# FrontPannel.net
KiCad netlist of a schematic drawn in Altium Designer
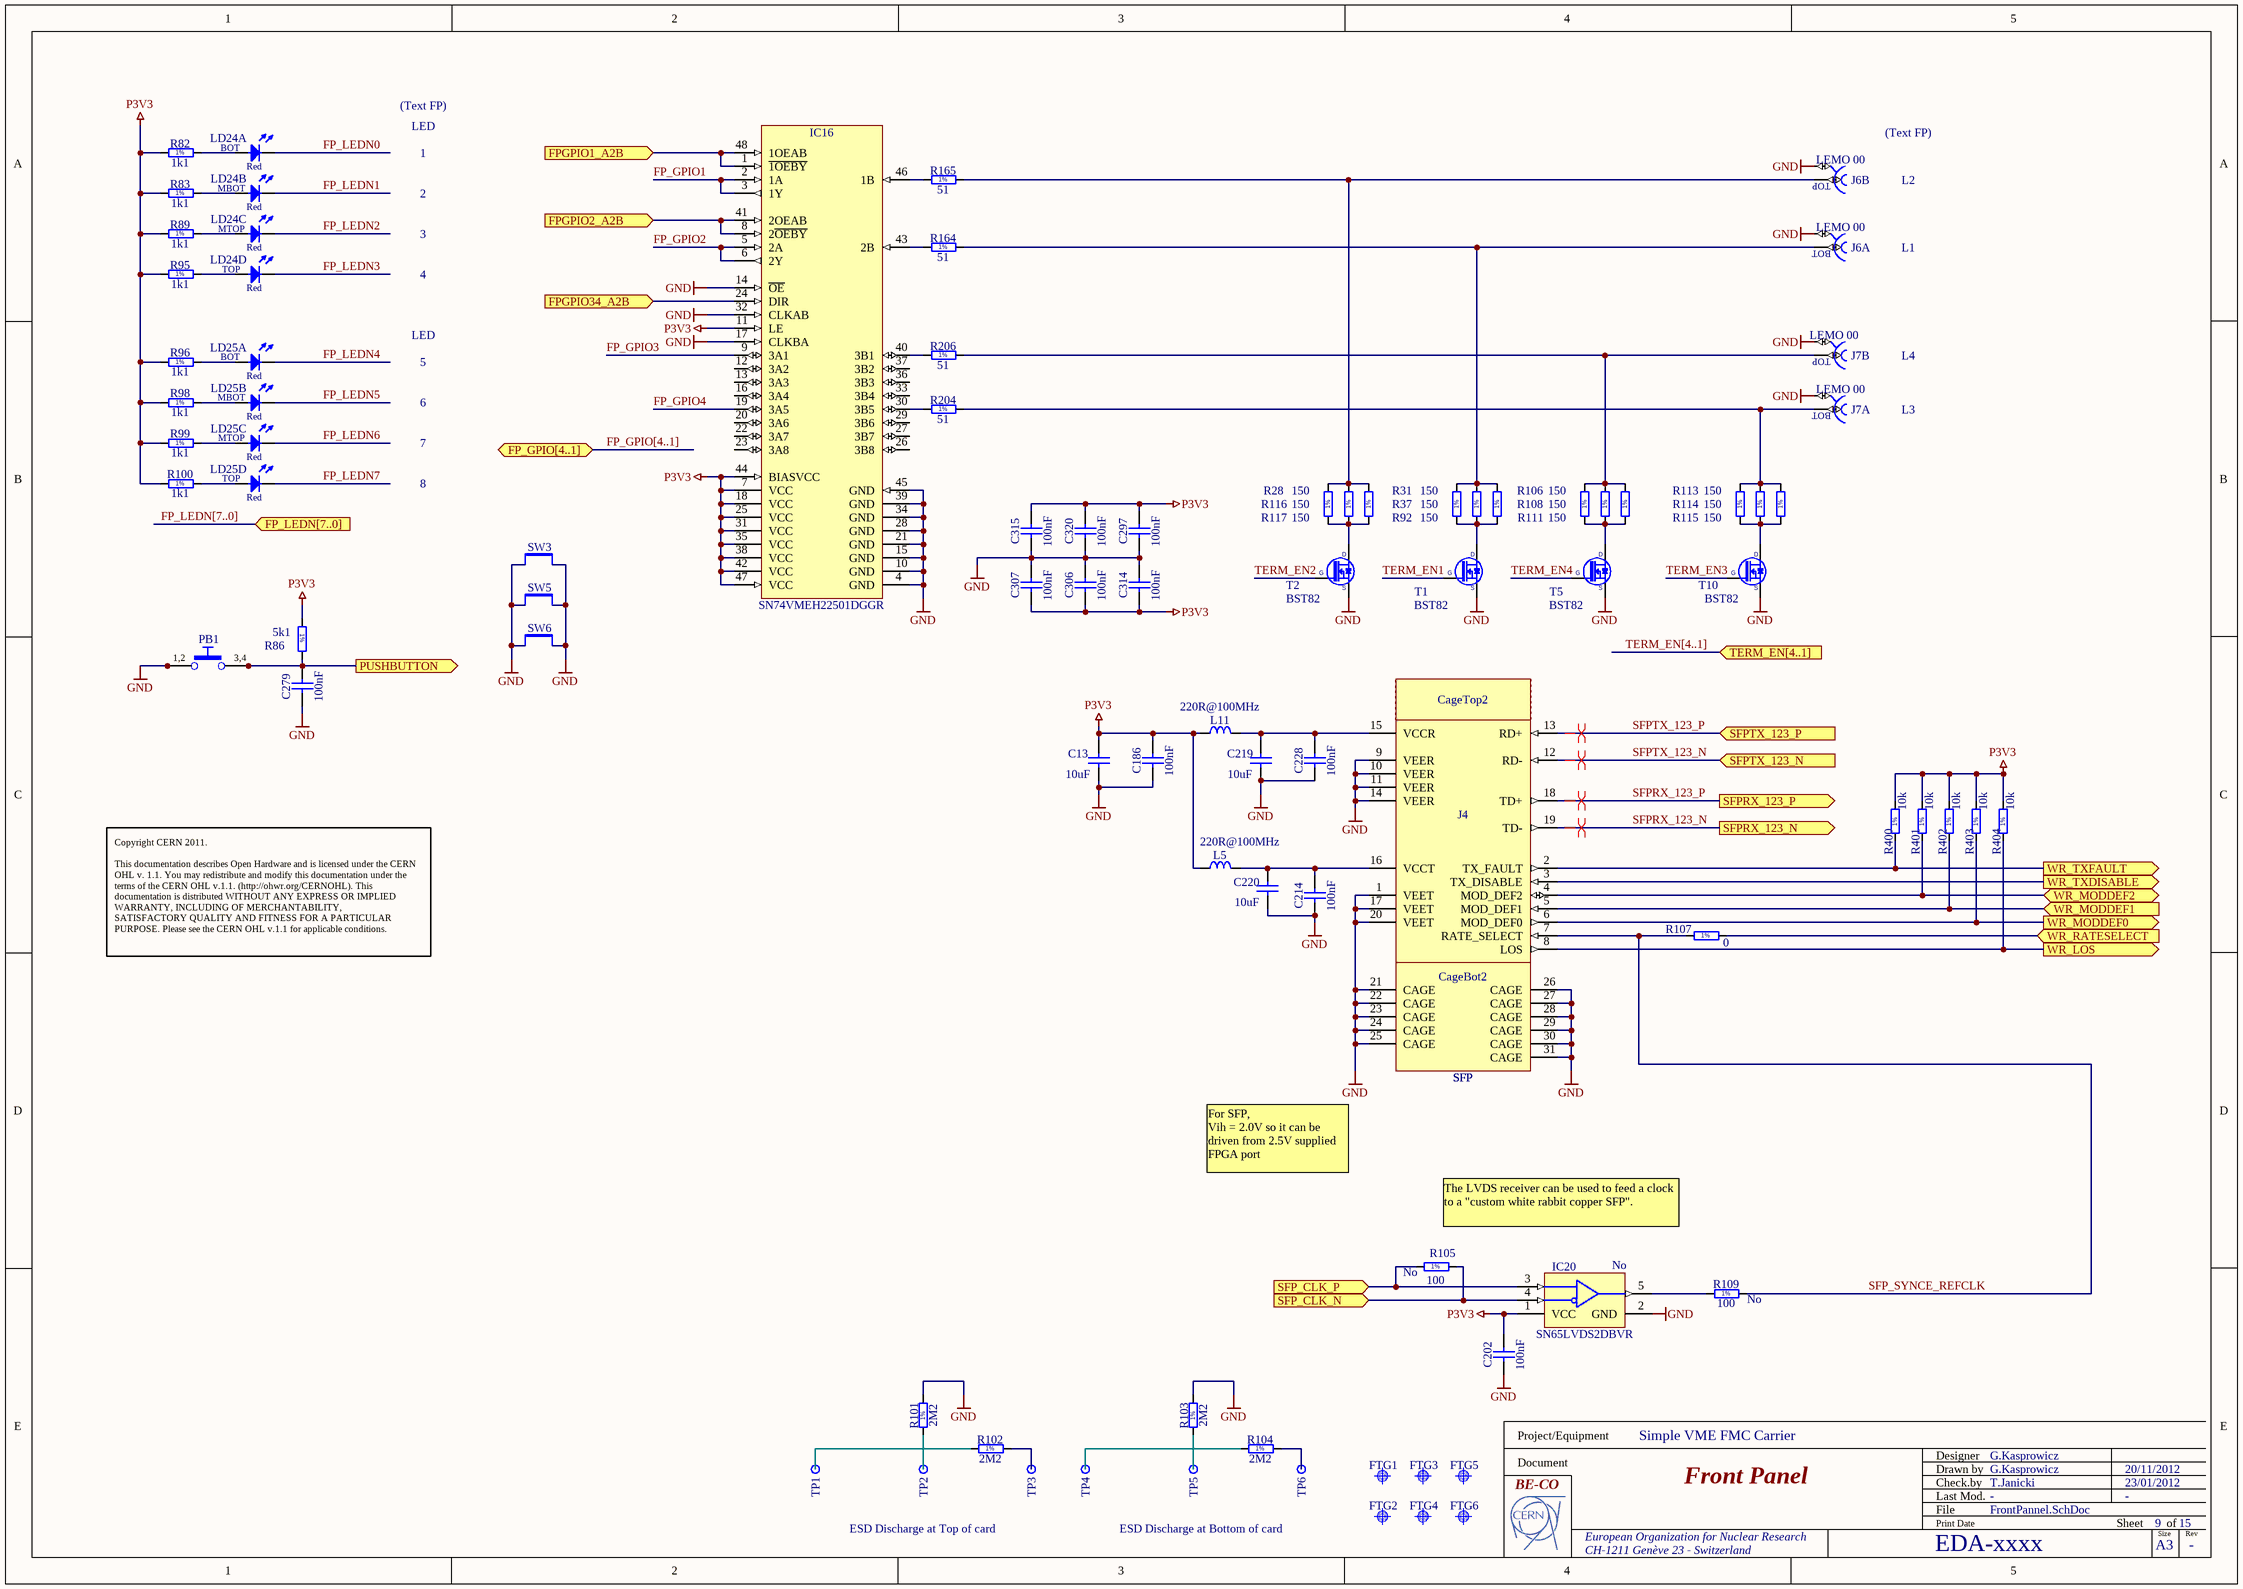
[diagram p0: FrontPannel.SchDoc]

(export (version "E")
  (design (tool "Eeschema 10.0.6"))
  (components
    (comp (ref "C13")
      (value "10uF")
      (footprint "CAPC3225X270N")
      (description "Non-polarised capacitor")
      (fields
        (field (name "PART NUMBER") "CC1210_10UF_25V_10%_X7R")
        (field (name "VOLTAGE") "25V")
        (field (name "AUTHOR") "CERN DEM JLC")
      )
      (libsource (lib "Capacitors") (part "Capacitor - non polarized"))
    )
    (comp (ref "C186")
      (value "100nF")
      (footprint "CAPC1005X55N")
      (description "Non-polarised capacitor")
      (fields
        (field (name "PART NUMBER") "CC0402_100NF_16V_10%_X7R")
        (field (name "VOLTAGE") "16V")
        (field (name "AUTHOR") "CERN DEM JLC")
      )
      (libsource (lib "Capacitors") (part "Capacitor - non polarized"))
    )
    (comp (ref "C202")
      (value "100nF")
      (footprint "CAPC1005X55N")
      (description "Non-polarised capacitor")
      (fields
        (field (name "PART NUMBER") "CC0402_100NF_16V_10%_X7R")
        (field (name "VOLTAGE") "16V")
        (field (name "AUTHOR") "CERN DEM JLC")
      )
      (libsource (lib "Capacitors") (part "Capacitor - non polarized"))
    )
    (comp (ref "C214")
      (value "100nF")
      (footprint "CAPC1005X55N")
      (description "Non-polarised capacitor")
      (fields
        (field (name "PART NUMBER") "CC0402_100NF_16V_10%_X7R")
        (field (name "VOLTAGE") "16V")
        (field (name "AUTHOR") "CERN DEM JLC")
      )
      (libsource (lib "Capacitors") (part "Capacitor - non polarized"))
    )
    (comp (ref "C219")
      (value "10uF")
      (footprint "CAPC3225X270N")
      (description "Non-polarised capacitor")
      (fields
        (field (name "PART NUMBER") "CC1210_10UF_25V_10%_X7R")
        (field (name "VOLTAGE") "25V")
        (field (name "AUTHOR") "CERN DEM JLC")
      )
      (libsource (lib "Capacitors") (part "Capacitor - non polarized"))
    )
    (comp (ref "C220")
      (value "10uF")
      (footprint "CAPC3225X270N")
      (description "Non-polarised capacitor")
      (fields
        (field (name "PART NUMBER") "CC1210_10UF_25V_10%_X7R")
        (field (name "VOLTAGE") "25V")
        (field (name "AUTHOR") "CERN DEM JLC")
      )
      (libsource (lib "Capacitors") (part "Capacitor - non polarized"))
    )
    (comp (ref "C228")
      (value "100nF")
      (footprint "CAPC1005X55N")
      (description "Non-polarised capacitor")
      (fields
        (field (name "PART NUMBER") "CC0402_100NF_16V_10%_X7R")
        (field (name "VOLTAGE") "16V")
        (field (name "AUTHOR") "CERN DEM JLC")
      )
      (libsource (lib "Capacitors") (part "Capacitor - non polarized"))
    )
    (comp (ref "C279")
      (value "100nF")
      (footprint "CAPC1005X55N")
      (description "Non-polarised capacitor")
      (fields
        (field (name "PART NUMBER") "CC0402_100NF_16V_10%_X7R")
        (field (name "VOLTAGE") "16V")
        (field (name "AUTHOR") "CERN DEM JLC")
      )
      (libsource (lib "Capacitors") (part "Capacitor - non polarized"))
    )
    (comp (ref "C297")
      (value "100nF")
      (footprint "CAPC1005X55N")
      (description "Non-polarised capacitor")
      (fields
        (field (name "PART NUMBER") "CC0402_100NF_16V_10%_X7R")
        (field (name "VOLTAGE") "16V")
        (field (name "AUTHOR") "CERN DEM JLC")
      )
      (libsource (lib "Capacitors") (part "Capacitor - non polarized"))
    )
    (comp (ref "C306")
      (value "100nF")
      (footprint "CAPC1005X55N")
      (description "Non-polarised capacitor")
      (fields
        (field (name "PART NUMBER") "CC0402_100NF_16V_10%_X7R")
        (field (name "VOLTAGE") "16V")
        (field (name "AUTHOR") "CERN DEM JLC")
      )
      (libsource (lib "Capacitors") (part "Capacitor - non polarized"))
    )
    (comp (ref "C307")
      (value "100nF")
      (footprint "CAPC1005X55N")
      (description "Non-polarised capacitor")
      (fields
        (field (name "PART NUMBER") "CC0402_100NF_16V_10%_X7R")
        (field (name "VOLTAGE") "16V")
        (field (name "AUTHOR") "CERN DEM JLC")
      )
      (libsource (lib "Capacitors") (part "Capacitor - non polarized"))
    )
    (comp (ref "C314")
      (value "100nF")
      (footprint "CAPC1005X55N")
      (description "Non-polarised capacitor")
      (fields
        (field (name "PART NUMBER") "CC0402_100NF_16V_10%_X7R")
        (field (name "VOLTAGE") "16V")
        (field (name "AUTHOR") "CERN DEM JLC")
      )
      (libsource (lib "Capacitors") (part "Capacitor - non polarized"))
    )
    (comp (ref "C315")
      (value "100nF")
      (footprint "CAPC1005X55N")
      (description "Non-polarised capacitor")
      (fields
        (field (name "PART NUMBER") "CC0402_100NF_16V_10%_X7R")
        (field (name "VOLTAGE") "16V")
        (field (name "AUTHOR") "CERN DEM JLC")
      )
      (libsource (lib "Capacitors") (part "Capacitor - non polarized"))
    )
    (comp (ref "C320")
      (value "100nF")
      (footprint "CAPC1005X55N")
      (description "Non-polarised capacitor")
      (fields
        (field (name "PART NUMBER") "CC0402_100NF_16V_10%_X7R")
        (field (name "VOLTAGE") "16V")
        (field (name "AUTHOR") "CERN DEM JLC")
      )
      (libsource (lib "Capacitors") (part "Capacitor - non polarized"))
    )
    (comp (ref "CageBot2")
      (value "SFP")
      (footprint "TYCO_6367034-1")
      (description "SFP  Cage Bottom (Small Form-factor Pluggable)")
      (fields
        (field (name "PART NUMBER") "TYCO_6367034-1")
        (field (name "MANUFACTURER") "TYCO ELECTRONICS")
        (field (name "AUTHOR") "CERN DEM JLC")
      )
      (libsource (lib "Connectors") (part "SFPx1_Cage Bottom"))
    )
    (comp (ref "CageTop2")
      (value "SFP")
      (footprint "TYCO_6367035-1")
      (description "SFP  Cage Top (Small Form-factor Pluggable)")
      (fields
        (field (name "PART NUMBER") "TYCO_6367035-1")
        (field (name "MANUFACTURER") "TYCO ELECTRONICS")
        (field (name "AUTHOR") "CERN DEM JLC")
      )
      (libsource (lib "Connectors") (part "SFPx1_Cage Top"))
    )
    (comp (ref "FTG1")
      (value "Use only in PCB")
      (footprint "FIDUCIAL_TOP_S100-200")
      (description "Fiducial Target")
      (fields (field (name "PART NUMBER") "FIDUCIAL_TARGET_S100-200") (field (name "AUTHOR") "CERN DEM JLC"))
      (libsource (lib "Eletro-mechanical") (part "Fiducial Target"))
    )
    (comp (ref "FTG2")
      (value "Use only in PCB")
      (footprint "FIDUCIAL_TOP_S100-200")
      (description "Fiducial Target")
      (fields (field (name "PART NUMBER") "FIDUCIAL_TARGET_S100-200") (field (name "AUTHOR") "CERN DEM JLC"))
      (libsource (lib "Eletro-mechanical") (part "Fiducial Target"))
    )
    (comp (ref "FTG3")
      (value "Use only in PCB")
      (footprint "FIDUCIAL_TOP_S100-200")
      (description "Fiducial Target")
      (fields (field (name "PART NUMBER") "FIDUCIAL_TARGET_S100-200") (field (name "AUTHOR") "CERN DEM JLC"))
      (libsource (lib "Eletro-mechanical") (part "Fiducial Target"))
    )
    (comp (ref "FTG4")
      (value "Use only in PCB")
      (footprint "FIDUCIAL_TOP_S100-200")
      (description "Fiducial Target")
      (fields (field (name "PART NUMBER") "FIDUCIAL_TARGET_S100-200") (field (name "AUTHOR") "CERN DEM JLC"))
      (libsource (lib "Eletro-mechanical") (part "Fiducial Target"))
    )
    (comp (ref "FTG5")
      (value "Use only in PCB")
      (footprint "FIDUCIAL_TOP_S100-200")
      (description "Fiducial Target")
      (fields (field (name "PART NUMBER") "FIDUCIAL_TARGET_S100-200") (field (name "AUTHOR") "CERN DEM JLC"))
      (libsource (lib "Eletro-mechanical") (part "Fiducial Target"))
    )
    (comp (ref "FTG6")
      (value "Use only in PCB")
      (footprint "FIDUCIAL_TOP_S100-200")
      (description "Fiducial Target")
      (fields (field (name "PART NUMBER") "FIDUCIAL_TARGET_S100-200") (field (name "AUTHOR") "CERN DEM JLC"))
      (libsource (lib "Eletro-mechanical") (part "Fiducial Target"))
    )
    (comp (ref "IC16")
      (value "SN74VMEH22501DGGR")
      (footprint "SOP50P810X120-48N")
      (description "8-Bit Universal Bus Transceiver and Two 1-Bit Bus Transceivers with 3-State Outputs")
      (fields (field (name "MANUFACTURER") "TEXAS INSTRUMENTS") (field (name "AUTHOR") "CERN DEM JLC"))
      (libsource (lib "ICs And Semiconductors") (part "74VMEH22501"))
    )
    (comp (ref "IC20")
      (value "SN65LVDS2DBVR")
      (footprint "SOT95P280X145-5N")
      (description "High-Speed Differential Line Receiver")
      (fields
        (field (name "MANUFACTURER") "TEXAS INSTRUMENTS")
        (field (name "MOUNTED") "No")
        (field (name "AUTHOR") "CERN DEM JLC")
      )
      (libsource (lib "ICs And Semiconductors") (part "SN65LVDS2DBVR"))
    )
    (comp (ref "J4")
      (value "SFP")
      (footprint "TYCO_1367073-1")
      (description "20 Position SFP  Connector (Small Form-factor Pluggable)")
      (fields
        (field (name "PART NUMBER") "TYCO_1367073-1")
        (field (name "MANUFACTURER") "TYCO ELECTRONICS")
        (field (name "AUTHOR") "CERN DEM JLC")
      )
      (libsource (lib "Connectors") (part "SFPx1"))
    )
    (comp (ref "J6")
      (value "LEMO 00")
      (footprint "LEMO_EPY.00.250.NTNY")
      (description "Dual Female Coax 1-2 Common Shield 3")
      (fields
        (field (name "PART NUMBER") "LEMO_EPY.00.250.NTNY")
        (field (name "MANUFACTURER") "LEMO")
        (field (name "AUTHOR") "CERN DEM JLC")
      )
      (libsource (lib "Connectors") (part "LEMO_EPY.00.250.NTN"))
    )
    (comp (ref "J7")
      (value "LEMO 00")
      (footprint "LEMO_EPY.00.250.NTNY")
      (description "Dual Female Coax 1-2 Common Shield 3")
      (fields
        (field (name "PART NUMBER") "LEMO_EPY.00.250.NTNY")
        (field (name "MANUFACTURER") "LEMO")
        (field (name "AUTHOR") "CERN DEM JLC")
      )
      (libsource (lib "Connectors") (part "LEMO_EPY.00.250.NTN"))
    )
    (comp (ref "L5")
      (value "220R@100MHz")
      (footprint "INDC2012X105N")
      (description "Inductor")
      (fields
        (field (name "PART NUMBER") "IND0805_MURATA_BLM21PG221SN1D")
        (field (name "POWER") "2A")
        (field (name "AUTHOR") "CERN DEM JLC")
      )
      (libsource (lib "Inductors & Transformers") (part "Inductor"))
    )
    (comp (ref "L11")
      (value "220R@100MHz")
      (footprint "INDC2012X105N")
      (description "Inductor")
      (fields
        (field (name "PART NUMBER") "IND0805_MURATA_BLM21PG221SN1D")
        (field (name "POWER") "2A")
        (field (name "AUTHOR") "CERN DEM JLC")
      )
      (libsource (lib "Inductors & Transformers") (part "Inductor"))
    )
    (comp (ref "LD24")
      (value "HE Red")
      (footprint "LED_BIVAR_H485CHDL")
      (description "LED x4 Red 1C2A-BOT_3C4A_5C6A_7C8A-TOP")
      (fields
        (field (name "PART NUMBER") "LED_BIVAR_H485CHDL")
        (field (name "MANUFACTURER") "BIVAR")
        (field (name "AUTHOR") "CERN DEM JLC")
      )
      (libsource (lib "ICs And Semiconductors") (part "LED x4 Red 1C2A-BOT_3C4A_5C6A_7C8A-TOP"))
    )
    (comp (ref "LD25")
      (value "HE Red")
      (footprint "LED_BIVAR_H485CHDL")
      (description "LED x4 Red 1C2A-BOT_3C4A_5C6A_7C8A-TOP")
      (fields
        (field (name "PART NUMBER") "LED_BIVAR_H485CHDL")
        (field (name "MANUFACTURER") "BIVAR")
        (field (name "AUTHOR") "CERN DEM JLC")
      )
      (libsource (lib "ICs And Semiconductors") (part "LED x4 Red 1C2A-BOT_3C4A_5C6A_7C8A-TOP"))
    )
    (comp (ref "PB1")
      (value "Push Button")
      (footprint "PB_TYCO_ALCOSWITCH_FSM2JSMA")
      (description "Push-Button Switch SPDT")
      (fields
        (field (name "PART NUMBER") "PB_TYCO_ALCOSWITCH_FSM2JSMA")
        (field (name "MANUFACTURER") "TYCO ALCOSWITCH")
        (field (name "AUTHOR") "CERN DEM JLC")
      )
      (libsource (lib "Eletro-mechanical") (part "PB SPST 12NO-34NO"))
    )
    (comp (ref "R28")
      (value "150")
      (footprint "RESC3216X65N")
      (description "Resistor - 1%")
      (fields
        (field (name "PART NUMBER") "R1206_150R_1%_0.25W_100PPM")
        (field (name "POWER") "0.25W")
        (field (name "AUTHOR") "CERN DEM JLC")
      )
      (libsource (lib "Resistors") (part "Resistor - 1%"))
    )
    (comp (ref "R31")
      (value "150")
      (footprint "RESC3216X65N")
      (description "Resistor - 1%")
      (fields
        (field (name "PART NUMBER") "R1206_150R_1%_0.25W_100PPM")
        (field (name "POWER") "0.25W")
        (field (name "AUTHOR") "CERN DEM JLC")
      )
      (libsource (lib "Resistors") (part "Resistor - 1%"))
    )
    (comp (ref "R37")
      (value "150")
      (footprint "RESC3216X65N")
      (description "Resistor - 1%")
      (fields
        (field (name "PART NUMBER") "R1206_150R_1%_0.25W_100PPM")
        (field (name "POWER") "0.25W")
        (field (name "AUTHOR") "CERN DEM JLC")
      )
      (libsource (lib "Resistors") (part "Resistor - 1%"))
    )
    (comp (ref "R82")
      (value "1k1")
      (footprint "RESC1608X55N")
      (description "Resistor - 1%")
      (fields
        (field (name "PART NUMBER") "R0603_1K1_1%_0.1W_100PPM")
        (field (name "POWER") "0.1W")
        (field (name "AUTHOR") "CERN DEM JLC")
      )
      (libsource (lib "Resistors") (part "Resistor - 1%"))
    )
    (comp (ref "R83")
      (value "1k1")
      (footprint "RESC1608X55N")
      (description "Resistor - 1%")
      (fields
        (field (name "PART NUMBER") "R0603_1K1_1%_0.1W_100PPM")
        (field (name "POWER") "0.1W")
        (field (name "AUTHOR") "CERN DEM JLC")
      )
      (libsource (lib "Resistors") (part "Resistor - 1%"))
    )
    (comp (ref "R86")
      (value "5k1")
      (footprint "RESC1608X55N")
      (description "Resistor - 1%")
      (fields
        (field (name "PART NUMBER") "R0603_5K1_1%_0.1W_100PPM")
        (field (name "POWER") "0.1W")
        (field (name "AUTHOR") "CERN DEM JLC")
      )
      (libsource (lib "Resistors") (part "Resistor - 1%"))
    )
    (comp (ref "R89")
      (value "1k1")
      (footprint "RESC1608X55N")
      (description "Resistor - 1%")
      (fields
        (field (name "PART NUMBER") "R0603_1K1_1%_0.1W_100PPM")
        (field (name "POWER") "0.1W")
        (field (name "AUTHOR") "CERN DEM JLC")
      )
      (libsource (lib "Resistors") (part "Resistor - 1%"))
    )
    (comp (ref "R92")
      (value "150")
      (footprint "RESC3216X65N")
      (description "Resistor - 1%")
      (fields
        (field (name "PART NUMBER") "R1206_150R_1%_0.25W_100PPM")
        (field (name "POWER") "0.25W")
        (field (name "AUTHOR") "CERN DEM JLC")
      )
      (libsource (lib "Resistors") (part "Resistor - 1%"))
    )
    (comp (ref "R95")
      (value "1k1")
      (footprint "RESC1608X55N")
      (description "Resistor - 1%")
      (fields
        (field (name "PART NUMBER") "R0603_1K1_1%_0.1W_100PPM")
        (field (name "POWER") "0.1W")
        (field (name "AUTHOR") "CERN DEM JLC")
      )
      (libsource (lib "Resistors") (part "Resistor - 1%"))
    )
    (comp (ref "R96")
      (value "1k1")
      (footprint "RESC1608X55N")
      (description "Resistor - 1%")
      (fields
        (field (name "PART NUMBER") "R0603_1K1_1%_0.1W_100PPM")
        (field (name "POWER") "0.1W")
        (field (name "AUTHOR") "CERN DEM JLC")
      )
      (libsource (lib "Resistors") (part "Resistor - 1%"))
    )
    (comp (ref "R98")
      (value "1k1")
      (footprint "RESC1608X55N")
      (description "Resistor - 1%")
      (fields
        (field (name "PART NUMBER") "R0603_1K1_1%_0.1W_100PPM")
        (field (name "POWER") "0.1W")
        (field (name "AUTHOR") "CERN DEM JLC")
      )
      (libsource (lib "Resistors") (part "Resistor - 1%"))
    )
    (comp (ref "R99")
      (value "1k1")
      (footprint "RESC1608X55N")
      (description "Resistor - 1%")
      (fields
        (field (name "PART NUMBER") "R0603_1K1_1%_0.1W_100PPM")
        (field (name "POWER") "0.1W")
        (field (name "AUTHOR") "CERN DEM JLC")
      )
      (libsource (lib "Resistors") (part "Resistor - 1%"))
    )
    (comp (ref "R100")
      (value "1k1")
      (footprint "RESC1608X55N")
      (description "Resistor - 1%")
      (fields
        (field (name "PART NUMBER") "R0603_1K1_1%_0.1W_100PPM")
        (field (name "POWER") "0.1W")
        (field (name "AUTHOR") "CERN DEM JLC")
      )
      (libsource (lib "Resistors") (part "Resistor - 1%"))
    )
    (comp (ref "R101")
      (value "2M2")
      (footprint "RESC2012X60N")
      (description "Resistor - 1%")
      (fields
        (field (name "PART NUMBER") "R0805_2M2_1%_0.125W_100PPM")
        (field (name "POWER") "0.125W")
        (field (name "AUTHOR") "CERN DEM JLC")
      )
      (libsource (lib "Resistors") (part "Resistor - 1%"))
    )
    (comp (ref "R102")
      (value "2M2")
      (footprint "RESC2012X60N")
      (description "Resistor - 1%")
      (fields
        (field (name "PART NUMBER") "R0805_2M2_1%_0.125W_100PPM")
        (field (name "POWER") "0.125W")
        (field (name "AUTHOR") "CERN DEM JLC")
      )
      (libsource (lib "Resistors") (part "Resistor - 1%"))
    )
    (comp (ref "R103")
      (value "2M2")
      (footprint "RESC2012X60N")
      (description "Resistor - 1%")
      (fields
        (field (name "PART NUMBER") "R0805_2M2_1%_0.125W_100PPM")
        (field (name "POWER") "0.125W")
        (field (name "AUTHOR") "CERN DEM JLC")
      )
      (libsource (lib "Resistors") (part "Resistor - 1%"))
    )
    (comp (ref "R104")
      (value "2M2")
      (footprint "RESC2012X60N")
      (description "Resistor - 1%")
      (fields
        (field (name "PART NUMBER") "R0805_2M2_1%_0.125W_100PPM")
        (field (name "POWER") "0.125W")
        (field (name "AUTHOR") "CERN DEM JLC")
      )
      (libsource (lib "Resistors") (part "Resistor - 1%"))
    )
    (comp (ref "R105")
      (value "100")
      (footprint "RESC1608X55N")
      (description "Resistor - 1%")
      (fields
        (field (name "PART NUMBER") "R0603_100R_1%_0.1W_100PPM")
        (field (name "POWER") "0.1W")
        (field (name "MOUNTED") "No")
        (field (name "AUTHOR") "CERN DEM JLC")
      )
      (libsource (lib "Resistors") (part "Resistor - 1%"))
    )
    (comp (ref "R106")
      (value "150")
      (footprint "RESC3216X65N")
      (description "Resistor - 1%")
      (fields
        (field (name "PART NUMBER") "R1206_150R_1%_0.25W_100PPM")
        (field (name "POWER") "0.25W")
        (field (name "AUTHOR") "CERN DEM JLC")
      )
      (libsource (lib "Resistors") (part "Resistor - 1%"))
    )
    (comp (ref "R107")
      (value "0")
      (footprint "RESC1608X55N")
      (description "Resistor - 1%")
      (fields
        (field (name "PART NUMBER") "R0603_0R_JUMPER")
        (field (name "MANUFACTURER") "GENERIC")
        (field (name "AUTHOR") "CERN DEM JLC")
      )
      (libsource (lib "Resistors") (part "Resistor - 1%"))
    )
    (comp (ref "R108")
      (value "150")
      (footprint "RESC3216X65N")
      (description "Resistor - 1%")
      (fields
        (field (name "PART NUMBER") "R1206_150R_1%_0.25W_100PPM")
        (field (name "POWER") "0.25W")
        (field (name "AUTHOR") "CERN DEM JLC")
      )
      (libsource (lib "Resistors") (part "Resistor - 1%"))
    )
    (comp (ref "R109")
      (value "100")
      (footprint "RESC1608X55N")
      (description "Resistor - 1%")
      (fields
        (field (name "PART NUMBER") "R0603_100R_1%_0.1W_100PPM")
        (field (name "POWER") "0.1W")
        (field (name "MOUNTED") "No")
        (field (name "AUTHOR") "CERN DEM JLC")
      )
      (libsource (lib "Resistors") (part "Resistor - 1%"))
    )
    (comp (ref "R111")
      (value "150")
      (footprint "RESC3216X65N")
      (description "Resistor - 1%")
      (fields
        (field (name "PART NUMBER") "R1206_150R_1%_0.25W_100PPM")
        (field (name "POWER") "0.25W")
        (field (name "AUTHOR") "CERN DEM JLC")
      )
      (libsource (lib "Resistors") (part "Resistor - 1%"))
    )
    (comp (ref "R113")
      (value "150")
      (footprint "RESC3216X65N")
      (description "Resistor - 1%")
      (fields
        (field (name "PART NUMBER") "R1206_150R_1%_0.25W_100PPM")
        (field (name "POWER") "0.25W")
        (field (name "AUTHOR") "CERN DEM JLC")
      )
      (libsource (lib "Resistors") (part "Resistor - 1%"))
    )
    (comp (ref "R114")
      (value "150")
      (footprint "RESC3216X65N")
      (description "Resistor - 1%")
      (fields
        (field (name "PART NUMBER") "R1206_150R_1%_0.25W_100PPM")
        (field (name "POWER") "0.25W")
        (field (name "AUTHOR") "CERN DEM JLC")
      )
      (libsource (lib "Resistors") (part "Resistor - 1%"))
    )
    (comp (ref "R115")
      (value "150")
      (footprint "RESC3216X65N")
      (description "Resistor - 1%")
      (fields
        (field (name "PART NUMBER") "R1206_150R_1%_0.25W_100PPM")
        (field (name "POWER") "0.25W")
        (field (name "AUTHOR") "CERN DEM JLC")
      )
      (libsource (lib "Resistors") (part "Resistor - 1%"))
    )
    (comp (ref "R116")
      (value "150")
      (footprint "RESC3216X65N")
      (description "Resistor - 1%")
      (fields
        (field (name "PART NUMBER") "R1206_150R_1%_0.25W_100PPM")
        (field (name "POWER") "0.25W")
        (field (name "AUTHOR") "CERN DEM JLC")
      )
      (libsource (lib "Resistors") (part "Resistor - 1%"))
    )
    (comp (ref "R117")
      (value "150")
      (footprint "RESC3216X65N")
      (description "Resistor - 1%")
      (fields
        (field (name "PART NUMBER") "R1206_150R_1%_0.25W_100PPM")
        (field (name "POWER") "0.25W")
        (field (name "AUTHOR") "CERN DEM JLC")
      )
      (libsource (lib "Resistors") (part "Resistor - 1%"))
    )
    (comp (ref "R164")
      (value "51")
      (footprint "RESC1005X40N")
      (description "Resistor - 1%")
      (fields
        (field (name "PART NUMBER") "R0402_51R_1%_0.0625W_100PPM")
        (field (name "POWER") "0.0625W")
        (field (name "AUTHOR") "CERN DEM JLC")
      )
      (libsource (lib "Resistors") (part "Resistor - 1%"))
    )
    (comp (ref "R165")
      (value "51")
      (footprint "RESC1005X40N")
      (description "Resistor - 1%")
      (fields
        (field (name "PART NUMBER") "R0402_51R_1%_0.0625W_100PPM")
        (field (name "POWER") "0.0625W")
        (field (name "AUTHOR") "CERN DEM JLC")
      )
      (libsource (lib "Resistors") (part "Resistor - 1%"))
    )
    (comp (ref "R204")
      (value "51")
      (footprint "RESC1005X40N")
      (description "Resistor - 1%")
      (fields
        (field (name "PART NUMBER") "R0402_51R_1%_0.0625W_100PPM")
        (field (name "POWER") "0.0625W")
        (field (name "AUTHOR") "CERN DEM JLC")
      )
      (libsource (lib "Resistors") (part "Resistor - 1%"))
    )
    (comp (ref "R206")
      (value "51")
      (footprint "RESC1005X40N")
      (description "Resistor - 1%")
      (fields
        (field (name "PART NUMBER") "R0402_51R_1%_0.0625W_100PPM")
        (field (name "POWER") "0.0625W")
        (field (name "AUTHOR") "CERN DEM JLC")
      )
      (libsource (lib "Resistors") (part "Resistor - 1%"))
    )
    (comp (ref "R400")
      (value "10k")
      (footprint "RESC1608X55N")
      (description "Resistor - 1%")
      (fields
        (field (name "PART NUMBER") "R0603_10K_1%_0.1W_100PPM")
        (field (name "POWER") "0.1W")
        (field (name "AUTHOR") "CERN DEM JLC")
      )
      (libsource (lib "Resistors") (part "Resistor - 1%"))
    )
    (comp (ref "R401")
      (value "10k")
      (footprint "RESC1608X55N")
      (description "Resistor - 1%")
      (fields
        (field (name "PART NUMBER") "R0603_10K_1%_0.1W_100PPM")
        (field (name "POWER") "0.1W")
        (field (name "AUTHOR") "CERN DEM JLC")
      )
      (libsource (lib "Resistors") (part "Resistor - 1%"))
    )
    (comp (ref "R402")
      (value "10k")
      (footprint "RESC1608X55N")
      (description "Resistor - 1%")
      (fields
        (field (name "PART NUMBER") "R0603_10K_1%_0.1W_100PPM")
        (field (name "POWER") "0.1W")
        (field (name "AUTHOR") "CERN DEM JLC")
      )
      (libsource (lib "Resistors") (part "Resistor - 1%"))
    )
    (comp (ref "R403")
      (value "10k")
      (footprint "RESC1608X55N")
      (description "Resistor - 1%")
      (fields
        (field (name "PART NUMBER") "R0603_10K_1%_0.1W_100PPM")
        (field (name "POWER") "0.1W")
        (field (name "AUTHOR") "CERN DEM JLC")
      )
      (libsource (lib "Resistors") (part "Resistor - 1%"))
    )
    (comp (ref "R404")
      (value "10k")
      (footprint "RESC1608X55N")
      (description "Resistor - 1%")
      (fields
        (field (name "PART NUMBER") "R0603_10K_1%_0.1W_100PPM")
        (field (name "POWER") "0.1W")
        (field (name "AUTHOR") "CERN DEM JLC")
      )
      (libsource (lib "Resistors") (part "Resistor - 1%"))
    )
    (comp (ref "SW3")
      (value "Jumper Type2")
      (footprint "COMATEL_313.0004.0.00.500")
      (description "Jumper 2 pins")
      (fields
        (field (name "PART NUMBER") "COMATEL_313.0004.0.00.500")
        (field (name "MANUFACTURER") "KONTEK COMATEL")
        (field (name "AUTHOR") "CERN DEM JMW")
      )
      (libsource (lib "Connectors") (part "Jumper Type2"))
    )
    (comp (ref "SW5")
      (value "Jumper Type2")
      (footprint "COMATEL_313.0004.0.00.500")
      (description "Jumper 2 pins")
      (fields
        (field (name "PART NUMBER") "COMATEL_313.0004.0.00.500")
        (field (name "MANUFACTURER") "KONTEK COMATEL")
        (field (name "AUTHOR") "CERN DEM JMW")
      )
      (libsource (lib "Connectors") (part "Jumper Type2"))
    )
    (comp (ref "SW6")
      (value "Jumper Type2")
      (footprint "COMATEL_313.0004.0.00.500")
      (description "Jumper 2 pins")
      (fields
        (field (name "PART NUMBER") "COMATEL_313.0004.0.00.500")
        (field (name "MANUFACTURER") "KONTEK COMATEL")
        (field (name "AUTHOR") "CERN DEM JMW")
      )
      (libsource (lib "Connectors") (part "Jumper Type2"))
    )
    (comp (ref "T1")
      (value "BST82")
      (footprint "SOT95P240X110-3N")
      (description "N-CHANNEL MOSFET WITH DIODE")
      (fields (field (name "MANUFACTURER") "NXP SEMICONDUCTORS") (field (name "AUTHOR") "CERN DEM JLC"))
      (libsource (lib "ICs And Semiconductors") (part "N-MOSFET-D 1G 2S 3D"))
    )
    (comp (ref "T2")
      (value "BST82")
      (footprint "SOT95P240X110-3N")
      (description "N-CHANNEL MOSFET WITH DIODE")
      (fields (field (name "MANUFACTURER") "NXP SEMICONDUCTORS") (field (name "AUTHOR") "CERN DEM JLC"))
      (libsource (lib "ICs And Semiconductors") (part "N-MOSFET-D 1G 2S 3D"))
    )
    (comp (ref "T5")
      (value "BST82")
      (footprint "SOT95P240X110-3N")
      (description "N-CHANNEL MOSFET WITH DIODE")
      (fields (field (name "MANUFACTURER") "NXP SEMICONDUCTORS") (field (name "AUTHOR") "CERN DEM JLC"))
      (libsource (lib "ICs And Semiconductors") (part "N-MOSFET-D 1G 2S 3D"))
    )
    (comp (ref "T10")
      (value "BST82")
      (footprint "SOT95P240X110-3N")
      (description "N-CHANNEL MOSFET WITH DIODE")
      (fields (field (name "MANUFACTURER") "NXP SEMICONDUCTORS") (field (name "AUTHOR") "CERN DEM JLC"))
      (libsource (lib "ICs And Semiconductors") (part "N-MOSFET-D 1G 2S 3D"))
    )
    (comp (ref "TP1")
      (value "Test Point")
      (footprint "TPS127")
      (fields (field (name "PART NUMBER") "SMD_PAD_1.27X1.27MM") (field (name "AUTHOR") "CERN DEM JLC"))
      (libsource (lib "Eletro-mechanical") (part "Test Point"))
    )
    (comp (ref "TP2")
      (value "Test Point")
      (footprint "TPS127")
      (fields (field (name "PART NUMBER") "SMD_PAD_1.27X1.27MM") (field (name "AUTHOR") "CERN DEM JLC"))
      (libsource (lib "Eletro-mechanical") (part "Test Point"))
    )
    (comp (ref "TP3")
      (value "Test Point")
      (footprint "TPS127")
      (fields (field (name "PART NUMBER") "SMD_PAD_1.27X1.27MM") (field (name "AUTHOR") "CERN DEM JLC"))
      (libsource (lib "Eletro-mechanical") (part "Test Point"))
    )
    (comp (ref "TP4")
      (value "Test Point")
      (footprint "TPS127")
      (fields (field (name "PART NUMBER") "SMD_PAD_1.27X1.27MM") (field (name "AUTHOR") "CERN DEM JLC"))
      (libsource (lib "Eletro-mechanical") (part "Test Point"))
    )
    (comp (ref "TP5")
      (value "Test Point")
      (footprint "TPS127")
      (fields (field (name "PART NUMBER") "SMD_PAD_1.27X1.27MM") (field (name "AUTHOR") "CERN DEM JLC"))
      (libsource (lib "Eletro-mechanical") (part "Test Point"))
    )
    (comp (ref "TP6")
      (value "Test Point")
      (footprint "TPS127")
      (fields (field (name "PART NUMBER") "SMD_PAD_1.27X1.27MM") (field (name "AUTHOR") "CERN DEM JLC"))
      (libsource (lib "Eletro-mechanical") (part "Test Point"))
    )
  )
  (nets
    (net (code "1") (name "/FPGPIO1_A2B") (class "Default")
      (node (ref "IC16") (pin "1") (pinfunction "~{1OEBY}_1") (pintype "input"))
      (node (ref "IC16") (pin "48") (pinfunction "1OEAB_48") (pintype "input"))
    )
    (net (code "2") (name "/FPGPIO2_A2B") (class "Default")
      (node (ref "IC16") (pin "41") (pinfunction "2OEAB_41") (pintype "input"))
      (node (ref "IC16") (pin "8") (pinfunction "2~{OEBY}_8") (pintype "input"))
    )
    (net (code "3") (name "/FPGPIO34_A2B") (class "Default")
      (node (ref "IC16") (pin "24") (pinfunction "DIR_24") (pintype "input"))
    )
    (net (code "4") (name "/FP_GPIO1") (class "Default")
      (node (ref "IC16") (pin "2") (pinfunction "1A_2") (pintype "input"))
      (node (ref "IC16") (pin "3") (pinfunction "1Y_3") (pintype "output"))
    )
    (net (code "5") (name "/FP_GPIO2") (class "Default")
      (node (ref "IC16") (pin "5") (pinfunction "2A_5") (pintype "input"))
      (node (ref "IC16") (pin "6") (pinfunction "2Y_6") (pintype "output"))
    )
    (net (code "6") (name "/FP_GPIO3") (class "Default")
      (node (ref "IC16") (pin "9") (pinfunction "3A1_9") (pintype "bidirectional"))
    )
    (net (code "7") (name "/FP_GPIO4") (class "Default")
      (node (ref "IC16") (pin "19") (pinfunction "3A5_19") (pintype "bidirectional"))
    )
    (net (code "9") (name "/FP_LEDN0") (class "Default")
      (node (ref "LD24") (pin "1") (pinfunction "C_1") (pintype "passive"))
    )
    (net (code "10") (name "/FP_LEDN1") (class "Default")
      (node (ref "LD24") (pin "3") (pinfunction "C_3") (pintype "passive"))
    )
    (net (code "11") (name "/FP_LEDN2") (class "Default")
      (node (ref "LD24") (pin "5") (pinfunction "C_5") (pintype "passive"))
    )
    (net (code "12") (name "/FP_LEDN3") (class "Default")
      (node (ref "LD24") (pin "7") (pinfunction "C_7") (pintype "passive"))
    )
    (net (code "13") (name "/FP_LEDN4") (class "Default")
      (node (ref "LD25") (pin "1") (pinfunction "C_1") (pintype "passive"))
    )
    (net (code "14") (name "/FP_LEDN5") (class "Default")
      (node (ref "LD25") (pin "3") (pinfunction "C_3") (pintype "passive"))
    )
    (net (code "15") (name "/FP_LEDN6") (class "Default")
      (node (ref "LD25") (pin "5") (pinfunction "C_5") (pintype "passive"))
    )
    (net (code "16") (name "/FP_LEDN7") (class "Default")
      (node (ref "LD25") (pin "7") (pinfunction "C_7") (pintype "passive"))
    )
    (net (code "18") (name "/PUSHBUTTON") (class "Default")
      (node (ref "C279") (pin "2") (pinfunction "2_2") (pintype "passive"))
      (node (ref "PB1") (pin "3") (pinfunction "3_3") (pintype "passive"))
      (node (ref "PB1") (pin "4") (pinfunction "4_4") (pintype "passive"))
      (node (ref "R86") (pin "2") (pinfunction "2_2") (pintype "passive"))
    )
    (net (code "19") (name "/SFPRX_123_N") (class "Default")
      (node (ref "J4") (pin "19") (pinfunction "TD-_19") (pintype "output"))
    )
    (net (code "20") (name "/SFPRX_123_P") (class "Default")
      (node (ref "J4") (pin "18") (pinfunction "TD+_18") (pintype "output"))
    )
    (net (code "21") (name "/SFPTX_123_N") (class "Default")
      (node (ref "J4") (pin "12") (pinfunction "RD-_12") (pintype "input"))
    )
    (net (code "22") (name "/SFPTX_123_P") (class "Default")
      (node (ref "J4") (pin "13") (pinfunction "RD+_13") (pintype "input"))
    )
    (net (code "23") (name "/SFP_CLK_N") (class "Default")
      (node (ref "IC20") (pin "4") (pinfunction "B_4") (pintype "input"))
      (node (ref "R105") (pin "2") (pinfunction "2_2") (pintype "passive"))
    )
    (net (code "24") (name "/SFP_CLK_P") (class "Default")
      (node (ref "IC20") (pin "3") (pinfunction "A_3") (pintype "input"))
      (node (ref "R105") (pin "1") (pinfunction "1_1") (pintype "passive"))
    )
    (net (code "25") (name "/SFP_SYNCE_REFCLK") (class "Default")
      (node (ref "J4") (pin "7") (pinfunction "RATE_SELECT_7") (pintype "input"))
      (node (ref "R107") (pin "1") (pinfunction "1_1") (pintype "passive"))
      (node (ref "R109") (pin "2") (pinfunction "2_2") (pintype "passive"))
    )
    (net (code "26") (name "/TERM_EN1") (class "Default")
      (node (ref "T1") (pin "1") (pinfunction "G_1") (pintype "passive"))
    )
    (net (code "27") (name "/TERM_EN2") (class "Default")
      (node (ref "T2") (pin "1") (pinfunction "G_1") (pintype "passive"))
    )
    (net (code "28") (name "/TERM_EN3") (class "Default")
      (node (ref "T10") (pin "1") (pinfunction "G_1") (pintype "passive"))
    )
    (net (code "29") (name "/TERM_EN4") (class "Default")
      (node (ref "T5") (pin "1") (pinfunction "G_1") (pintype "passive"))
    )
    (net (code "31") (name "/WR_LOS") (class "Default")
      (node (ref "J4") (pin "8") (pinfunction "LOS_8") (pintype "output"))
      (node (ref "R404") (pin "1") (pinfunction "1_1") (pintype "passive"))
    )
    (net (code "32") (name "/WR_MODDEF0") (class "Default")
      (node (ref "J4") (pin "6") (pinfunction "MOD_DEF0_6") (pintype "output"))
      (node (ref "R403") (pin "1") (pinfunction "1_1") (pintype "passive"))
    )
    (net (code "33") (name "/WR_MODDEF1") (class "Default")
      (node (ref "J4") (pin "5") (pinfunction "MOD_DEF1_5") (pintype "input"))
      (node (ref "R402") (pin "1") (pinfunction "1_1") (pintype "passive"))
    )
    (net (code "34") (name "/WR_MODDEF2") (class "Default")
      (node (ref "J4") (pin "4") (pinfunction "MOD_DEF2_4") (pintype "bidirectional"))
      (node (ref "R401") (pin "1") (pinfunction "1_1") (pintype "passive"))
    )
    (net (code "35") (name "/WR_RATESELECT") (class "Default")
      (node (ref "R107") (pin "2") (pinfunction "2_2") (pintype "passive"))
    )
    (net (code "36") (name "/WR_TXDISABLE") (class "Default")
      (node (ref "J4") (pin "3") (pinfunction "TX_DISABLE_3") (pintype "input"))
    )
    (net (code "37") (name "/WR_TXFAULT") (class "Default")
      (node (ref "J4") (pin "2") (pinfunction "TX_FAULT_2") (pintype "output"))
      (node (ref "R400") (pin "1") (pinfunction "1_1") (pintype "passive"))
    )
    (net (code "38") (name "GND") (class "Default")
      (node (ref "C13") (pin "2") (pinfunction "2_2") (pintype "passive"))
      (node (ref "C186") (pin "2") (pinfunction "2_2") (pintype "passive"))
      (node (ref "C202") (pin "1") (pinfunction "1_1") (pintype "passive"))
      (node (ref "C214") (pin "2") (pinfunction "2_2") (pintype "passive"))
      (node (ref "C219") (pin "2") (pinfunction "2_2") (pintype "passive"))
      (node (ref "C220") (pin "2") (pinfunction "2_2") (pintype "passive"))
      (node (ref "C228") (pin "2") (pinfunction "2_2") (pintype "passive"))
      (node (ref "C279") (pin "1") (pinfunction "1_1") (pintype "passive"))
      (node (ref "C297") (pin "1") (pinfunction "1_1") (pintype "passive"))
      (node (ref "C306") (pin "2") (pinfunction "2_2") (pintype "passive"))
      (node (ref "C307") (pin "2") (pinfunction "2_2") (pintype "passive"))
      (node (ref "C314") (pin "2") (pinfunction "2_2") (pintype "passive"))
      (node (ref "C315") (pin "1") (pinfunction "1_1") (pintype "passive"))
      (node (ref "C320") (pin "1") (pinfunction "1_1") (pintype "passive"))
      (node (ref "CageBot2") (pin "21") (pinfunction "CAGE_21") (pintype "power_in"))
      (node (ref "CageBot2") (pin "22") (pinfunction "CAGE_22") (pintype "power_in"))
      (node (ref "CageBot2") (pin "23") (pinfunction "CAGE_23") (pintype "power_in"))
      (node (ref "CageBot2") (pin "24") (pinfunction "CAGE_24") (pintype "power_in"))
      (node (ref "CageBot2") (pin "25") (pinfunction "CAGE_25") (pintype "power_in"))
      (node (ref "CageBot2") (pin "26") (pinfunction "CAGE_26") (pintype "power_in"))
      (node (ref "CageBot2") (pin "27") (pinfunction "CAGE_27") (pintype "power_in"))
      (node (ref "CageBot2") (pin "28") (pinfunction "CAGE_28") (pintype "power_in"))
      (node (ref "CageBot2") (pin "29") (pinfunction "CAGE_29") (pintype "power_in"))
      (node (ref "CageBot2") (pin "30") (pinfunction "CAGE_30") (pintype "power_in"))
      (node (ref "CageBot2") (pin "31") (pinfunction "CAGE_31") (pintype "power_in"))
      (node (ref "IC16") (pin "10") (pinfunction "GND_10") (pintype "power_in"))
      (node (ref "IC16") (pin "14") (pinfunction "~{OE}_14") (pintype "input"))
      (node (ref "IC16") (pin "15") (pinfunction "GND_15") (pintype "power_in"))
      (node (ref "IC16") (pin "17") (pinfunction "CLKBA_17") (pintype "input"))
      (node (ref "IC16") (pin "21") (pinfunction "GND_21") (pintype "power_in"))
      (node (ref "IC16") (pin "28") (pinfunction "GND_28") (pintype "power_in"))
      (node (ref "IC16") (pin "32") (pinfunction "CLKAB_32") (pintype "input"))
      (node (ref "IC16") (pin "34") (pinfunction "GND_34") (pintype "power_in"))
      (node (ref "IC16") (pin "39") (pinfunction "GND_39") (pintype "power_in"))
      (node (ref "IC16") (pin "4") (pinfunction "GND_4") (pintype "power_in"))
      (node (ref "IC16") (pin "45") (pinfunction "GND_45") (pintype "input"))
      (node (ref "IC20") (pin "2") (pinfunction "GND_2") (pintype "power_in"))
      (node (ref "J4") (pin "1") (pinfunction "VEET_1") (pintype "power_in"))
      (node (ref "J4") (pin "10") (pinfunction "VEER_10") (pintype "power_in"))
      (node (ref "J4") (pin "11") (pinfunction "VEER_11") (pintype "power_in"))
      (node (ref "J4") (pin "14") (pinfunction "VEER_14") (pintype "power_in"))
      (node (ref "J4") (pin "17") (pinfunction "VEET_17") (pintype "power_in"))
      (node (ref "J4") (pin "20") (pinfunction "VEET_20") (pintype "power_in"))
      (node (ref "J4") (pin "9") (pinfunction "VEER_9") (pintype "power_in"))
      (node (ref "J6") (pin "3") (pinfunction "3_3") (pintype "bidirectional"))
      (node (ref "J7") (pin "3") (pinfunction "3_3") (pintype "bidirectional"))
      (node (ref "PB1") (pin "1") (pinfunction "1_1") (pintype "passive"))
      (node (ref "PB1") (pin "2") (pinfunction "2_2") (pintype "passive"))
      (node (ref "R101") (pin "2") (pinfunction "2_2") (pintype "passive"))
      (node (ref "R103") (pin "2") (pinfunction "2_2") (pintype "passive"))
      (node (ref "SW3") (pin "1") (pinfunction "1_1") (pintype "bidirectional"))
      (node (ref "SW3") (pin "2") (pinfunction "2_2") (pintype "bidirectional"))
      (node (ref "SW5") (pin "1") (pinfunction "1_1") (pintype "bidirectional"))
      (node (ref "SW5") (pin "2") (pinfunction "2_2") (pintype "bidirectional"))
      (node (ref "SW6") (pin "1") (pinfunction "1_1") (pintype "bidirectional"))
      (node (ref "SW6") (pin "2") (pinfunction "2_2") (pintype "bidirectional"))
      (node (ref "T1") (pin "2") (pinfunction "S_2") (pintype "passive"))
      (node (ref "T10") (pin "2") (pinfunction "S_2") (pintype "passive"))
      (node (ref "T2") (pin "2") (pinfunction "S_2") (pintype "passive"))
      (node (ref "T5") (pin "2") (pinfunction "S_2") (pintype "passive"))
    )
    (net (code "39") (name "Net-(IC16-1B)") (class "Default")
      (node (ref "IC16") (pin "46") (pinfunction "1B_46") (pintype "input"))
      (node (ref "R165") (pin "1") (pinfunction "1_1") (pintype "passive"))
    )
    (net (code "40") (name "Net-(IC16-2B)") (class "Default")
      (node (ref "IC16") (pin "43") (pinfunction "2B_43") (pintype "input"))
      (node (ref "R164") (pin "1") (pinfunction "1_1") (pintype "passive"))
    )
    (net (code "41") (name "Net-(IC16-3B1)") (class "Default")
      (node (ref "IC16") (pin "40") (pinfunction "3B1_40") (pintype "bidirectional"))
      (node (ref "R206") (pin "1") (pinfunction "1_1") (pintype "passive"))
    )
    (net (code "42") (name "Net-(IC16-3B5)") (class "Default")
      (node (ref "IC16") (pin "30") (pinfunction "3B5_30") (pintype "bidirectional"))
      (node (ref "R204") (pin "1") (pinfunction "1_1") (pintype "passive"))
    )
    (net (code "43") (name "Net-(IC20-R)") (class "Default")
      (node (ref "IC20") (pin "5") (pinfunction "R_5") (pintype "output"))
      (node (ref "R109") (pin "1") (pinfunction "1_1") (pintype "passive"))
    )
    (net (code "44") (name "Net-(J4-VCCR)") (class "Default")
      (node (ref "C219") (pin "1") (pinfunction "1_1") (pintype "passive"))
      (node (ref "C228") (pin "1") (pinfunction "1_1") (pintype "passive"))
      (node (ref "J4") (pin "15") (pinfunction "VCCR_15") (pintype "power_in"))
      (node (ref "L11") (pin "2") (pinfunction "2_2") (pintype "passive"))
    )
    (net (code "45") (name "Net-(J4-VCCT)") (class "Default")
      (node (ref "C214") (pin "1") (pinfunction "1_1") (pintype "passive"))
      (node (ref "C220") (pin "1") (pinfunction "1_1") (pintype "passive"))
      (node (ref "J4") (pin "16") (pinfunction "VCCT_16") (pintype "power_in"))
      (node (ref "L5") (pin "2") (pinfunction "2_2") (pintype "passive"))
    )
    (net (code "46") (name "Net-(J6-Pad1)") (class "Default")
      (node (ref "J6") (pin "1") (pinfunction "1_1") (pintype "bidirectional"))
      (node (ref "R164") (pin "2") (pinfunction "2_2") (pintype "passive"))
      (node (ref "R31") (pin "2") (pinfunction "2_2") (pintype "passive"))
      (node (ref "R37") (pin "2") (pinfunction "2_2") (pintype "passive"))
      (node (ref "R92") (pin "2") (pinfunction "2_2") (pintype "passive"))
    )
    (net (code "47") (name "Net-(J6-Pad2)") (class "Default")
      (node (ref "J6") (pin "2") (pinfunction "2_2") (pintype "bidirectional"))
      (node (ref "R116") (pin "2") (pinfunction "2_2") (pintype "passive"))
      (node (ref "R117") (pin "2") (pinfunction "2_2") (pintype "passive"))
      (node (ref "R165") (pin "2") (pinfunction "2_2") (pintype "passive"))
      (node (ref "R28") (pin "2") (pinfunction "2_2") (pintype "passive"))
    )
    (net (code "48") (name "Net-(J7-Pad1)") (class "Default")
      (node (ref "J7") (pin "1") (pinfunction "1_1") (pintype "bidirectional"))
      (node (ref "R113") (pin "2") (pinfunction "2_2") (pintype "passive"))
      (node (ref "R114") (pin "2") (pinfunction "2_2") (pintype "passive"))
      (node (ref "R115") (pin "2") (pinfunction "2_2") (pintype "passive"))
      (node (ref "R204") (pin "2") (pinfunction "2_2") (pintype "passive"))
    )
    (net (code "49") (name "Net-(J7-Pad2)") (class "Default")
      (node (ref "J7") (pin "2") (pinfunction "2_2") (pintype "bidirectional"))
      (node (ref "R106") (pin "2") (pinfunction "2_2") (pintype "passive"))
      (node (ref "R108") (pin "2") (pinfunction "2_2") (pintype "passive"))
      (node (ref "R111") (pin "2") (pinfunction "2_2") (pintype "passive"))
      (node (ref "R206") (pin "2") (pinfunction "2_2") (pintype "passive"))
    )
    (net (code "50") (name "Net-(LD24A-A)") (class "Default")
      (node (ref "LD24") (pin "2") (pinfunction "A_2") (pintype "passive"))
      (node (ref "R82") (pin "2") (pinfunction "2_2") (pintype "passive"))
    )
    (net (code "51") (name "Net-(LD24B-A)") (class "Default")
      (node (ref "LD24") (pin "4") (pinfunction "A_4") (pintype "passive"))
      (node (ref "R83") (pin "2") (pinfunction "2_2") (pintype "passive"))
    )
    (net (code "52") (name "Net-(LD24C-A)") (class "Default")
      (node (ref "LD24") (pin "6") (pinfunction "A_6") (pintype "passive"))
      (node (ref "R89") (pin "2") (pinfunction "2_2") (pintype "passive"))
    )
    (net (code "53") (name "Net-(LD24D-A)") (class "Default")
      (node (ref "LD24") (pin "8") (pinfunction "A_8") (pintype "passive"))
      (node (ref "R95") (pin "2") (pinfunction "2_2") (pintype "passive"))
    )
    (net (code "54") (name "Net-(LD25A-A)") (class "Default")
      (node (ref "LD25") (pin "2") (pinfunction "A_2") (pintype "passive"))
      (node (ref "R96") (pin "2") (pinfunction "2_2") (pintype "passive"))
    )
    (net (code "55") (name "Net-(LD25B-A)") (class "Default")
      (node (ref "LD25") (pin "4") (pinfunction "A_4") (pintype "passive"))
      (node (ref "R98") (pin "2") (pinfunction "2_2") (pintype "passive"))
    )
    (net (code "56") (name "Net-(LD25C-A)") (class "Default")
      (node (ref "LD25") (pin "6") (pinfunction "A_6") (pintype "passive"))
      (node (ref "R99") (pin "2") (pinfunction "2_2") (pintype "passive"))
    )
    (net (code "57") (name "Net-(LD25D-A)") (class "Default")
      (node (ref "LD25") (pin "8") (pinfunction "A_8") (pintype "passive"))
      (node (ref "R100") (pin "2") (pinfunction "2_2") (pintype "passive"))
    )
    (net (code "58") (name "Net-(R101-Pad1)") (class "Default")
      (node (ref "R101") (pin "1") (pinfunction "1_1") (pintype "passive"))
      (node (ref "TP2") (pin "1") (pinfunction "1_1") (pintype "bidirectional"))
    )
    (net (code "59") (name "Net-(R102-Pad1)") (class "Default")
      (node (ref "R102") (pin "1") (pinfunction "1_1") (pintype "passive"))
      (node (ref "TP1") (pin "1") (pinfunction "1_1") (pintype "bidirectional"))
    )
    (net (code "60") (name "Net-(R102-Pad2)") (class "Default")
      (node (ref "R102") (pin "2") (pinfunction "2_2") (pintype "passive"))
      (node (ref "TP3") (pin "1") (pinfunction "1_1") (pintype "bidirectional"))
    )
    (net (code "61") (name "Net-(R103-Pad1)") (class "Default")
      (node (ref "R103") (pin "1") (pinfunction "1_1") (pintype "passive"))
      (node (ref "TP5") (pin "1") (pinfunction "1_1") (pintype "bidirectional"))
    )
    (net (code "62") (name "Net-(R104-Pad1)") (class "Default")
      (node (ref "R104") (pin "1") (pinfunction "1_1") (pintype "passive"))
      (node (ref "TP4") (pin "1") (pinfunction "1_1") (pintype "bidirectional"))
    )
    (net (code "63") (name "Net-(R104-Pad2)") (class "Default")
      (node (ref "R104") (pin "2") (pinfunction "2_2") (pintype "passive"))
      (node (ref "TP6") (pin "1") (pinfunction "1_1") (pintype "bidirectional"))
    )
    (net (code "64") (name "Net-(T1-D)") (class "Default")
      (node (ref "R31") (pin "1") (pinfunction "1_1") (pintype "passive"))
      (node (ref "R37") (pin "1") (pinfunction "1_1") (pintype "passive"))
      (node (ref "R92") (pin "1") (pinfunction "1_1") (pintype "passive"))
      (node (ref "T1") (pin "3") (pinfunction "D_3") (pintype "passive"))
    )
    (net (code "65") (name "Net-(T2-D)") (class "Default")
      (node (ref "R116") (pin "1") (pinfunction "1_1") (pintype "passive"))
      (node (ref "R117") (pin "1") (pinfunction "1_1") (pintype "passive"))
      (node (ref "R28") (pin "1") (pinfunction "1_1") (pintype "passive"))
      (node (ref "T2") (pin "3") (pinfunction "D_3") (pintype "passive"))
    )
    (net (code "66") (name "Net-(T5-D)") (class "Default")
      (node (ref "R106") (pin "1") (pinfunction "1_1") (pintype "passive"))
      (node (ref "R108") (pin "1") (pinfunction "1_1") (pintype "passive"))
      (node (ref "R111") (pin "1") (pinfunction "1_1") (pintype "passive"))
      (node (ref "T5") (pin "3") (pinfunction "D_3") (pintype "passive"))
    )
    (net (code "67") (name "Net-(T10-D)") (class "Default")
      (node (ref "R113") (pin "1") (pinfunction "1_1") (pintype "passive"))
      (node (ref "R114") (pin "1") (pinfunction "1_1") (pintype "passive"))
      (node (ref "R115") (pin "1") (pinfunction "1_1") (pintype "passive"))
      (node (ref "T10") (pin "3") (pinfunction "D_3") (pintype "passive"))
    )
    (net (code "68") (name "P3V3") (class "Default")
      (node (ref "C13") (pin "1") (pinfunction "1_1") (pintype "passive"))
      (node (ref "C186") (pin "1") (pinfunction "1_1") (pintype "passive"))
      (node (ref "C202") (pin "2") (pinfunction "2_2") (pintype "passive"))
      (node (ref "C297") (pin "2") (pinfunction "2_2") (pintype "passive"))
      (node (ref "C306") (pin "1") (pinfunction "1_1") (pintype "passive"))
      (node (ref "C307") (pin "1") (pinfunction "1_1") (pintype "passive"))
      (node (ref "C314") (pin "1") (pinfunction "1_1") (pintype "passive"))
      (node (ref "C315") (pin "2") (pinfunction "2_2") (pintype "passive"))
      (node (ref "C320") (pin "2") (pinfunction "2_2") (pintype "passive"))
      (node (ref "IC16") (pin "11") (pinfunction "LE_11") (pintype "input"))
      (node (ref "IC16") (pin "18") (pinfunction "VCC_18") (pintype "power_in"))
      (node (ref "IC16") (pin "25") (pinfunction "VCC_25") (pintype "power_in"))
      (node (ref "IC16") (pin "31") (pinfunction "VCC_31") (pintype "power_in"))
      (node (ref "IC16") (pin "35") (pinfunction "VCC_35") (pintype "power_in"))
      (node (ref "IC16") (pin "38") (pinfunction "VCC_38") (pintype "power_in"))
      (node (ref "IC16") (pin "42") (pinfunction "VCC_42") (pintype "power_in"))
      (node (ref "IC16") (pin "44") (pinfunction "BIASVCC_44") (pintype "input"))
      (node (ref "IC16") (pin "47") (pinfunction "VCC_47") (pintype "input"))
      (node (ref "IC16") (pin "7") (pinfunction "VCC_7") (pintype "power_in"))
      (node (ref "IC20") (pin "1") (pinfunction "VCC_1") (pintype "power_in"))
      (node (ref "L11") (pin "1") (pinfunction "1_1") (pintype "passive"))
      (node (ref "L5") (pin "1") (pinfunction "1_1") (pintype "passive"))
      (node (ref "R100") (pin "1") (pinfunction "1_1") (pintype "passive"))
      (node (ref "R400") (pin "2") (pinfunction "2_2") (pintype "passive"))
      (node (ref "R401") (pin "2") (pinfunction "2_2") (pintype "passive"))
      (node (ref "R402") (pin "2") (pinfunction "2_2") (pintype "passive"))
      (node (ref "R403") (pin "2") (pinfunction "2_2") (pintype "passive"))
      (node (ref "R404") (pin "2") (pinfunction "2_2") (pintype "passive"))
      (node (ref "R82") (pin "1") (pinfunction "1_1") (pintype "passive"))
      (node (ref "R83") (pin "1") (pinfunction "1_1") (pintype "passive"))
      (node (ref "R86") (pin "1") (pinfunction "1_1") (pintype "passive"))
      (node (ref "R89") (pin "1") (pinfunction "1_1") (pintype "passive"))
      (node (ref "R95") (pin "1") (pinfunction "1_1") (pintype "passive"))
      (node (ref "R96") (pin "1") (pinfunction "1_1") (pintype "passive"))
      (node (ref "R98") (pin "1") (pinfunction "1_1") (pintype "passive"))
      (node (ref "R99") (pin "1") (pinfunction "1_1") (pintype "passive"))
    )
    (net (code "69") (name "unconnected-(IC16-3A2-Pad12)") (class "Default")
      (node (ref "IC16") (pin "12") (pinfunction "3A2_12") (pintype "bidirectional"))
    )
    (net (code "70") (name "unconnected-(IC16-3A3-Pad13)") (class "Default")
      (node (ref "IC16") (pin "13") (pinfunction "3A3_13") (pintype "bidirectional"))
    )
    (net (code "71") (name "unconnected-(IC16-3A4-Pad16)") (class "Default")
      (node (ref "IC16") (pin "16") (pinfunction "3A4_16") (pintype "bidirectional"))
    )
    (net (code "72") (name "unconnected-(IC16-3A6-Pad20)") (class "Default")
      (node (ref "IC16") (pin "20") (pinfunction "3A6_20") (pintype "bidirectional"))
    )
    (net (code "73") (name "unconnected-(IC16-3A7-Pad22)") (class "Default")
      (node (ref "IC16") (pin "22") (pinfunction "3A7_22") (pintype "bidirectional"))
    )
    (net (code "74") (name "unconnected-(IC16-3A8-Pad23)") (class "Default")
      (node (ref "IC16") (pin "23") (pinfunction "3A8_23") (pintype "bidirectional"))
    )
    (net (code "75") (name "unconnected-(IC16-3B2-Pad37)") (class "Default")
      (node (ref "IC16") (pin "37") (pinfunction "3B2_37") (pintype "bidirectional"))
    )
    (net (code "76") (name "unconnected-(IC16-3B3-Pad36)") (class "Default")
      (node (ref "IC16") (pin "36") (pinfunction "3B3_36") (pintype "bidirectional"))
    )
    (net (code "77") (name "unconnected-(IC16-3B4-Pad33)") (class "Default")
      (node (ref "IC16") (pin "33") (pinfunction "3B4_33") (pintype "bidirectional"))
    )
    (net (code "78") (name "unconnected-(IC16-3B6-Pad29)") (class "Default")
      (node (ref "IC16") (pin "29") (pinfunction "3B6_29") (pintype "bidirectional"))
    )
    (net (code "79") (name "unconnected-(IC16-3B7-Pad27)") (class "Default")
      (node (ref "IC16") (pin "27") (pinfunction "3B7_27") (pintype "bidirectional"))
    )
    (net (code "80") (name "unconnected-(IC16-3B8-Pad26)") (class "Default")
      (node (ref "IC16") (pin "26") (pinfunction "3B8_26") (pintype "bidirectional"))
    )
  )
)
